# Stepper_Driver_Sheet4.net
KiCad netlist of a schematic drawn in Altium Designer
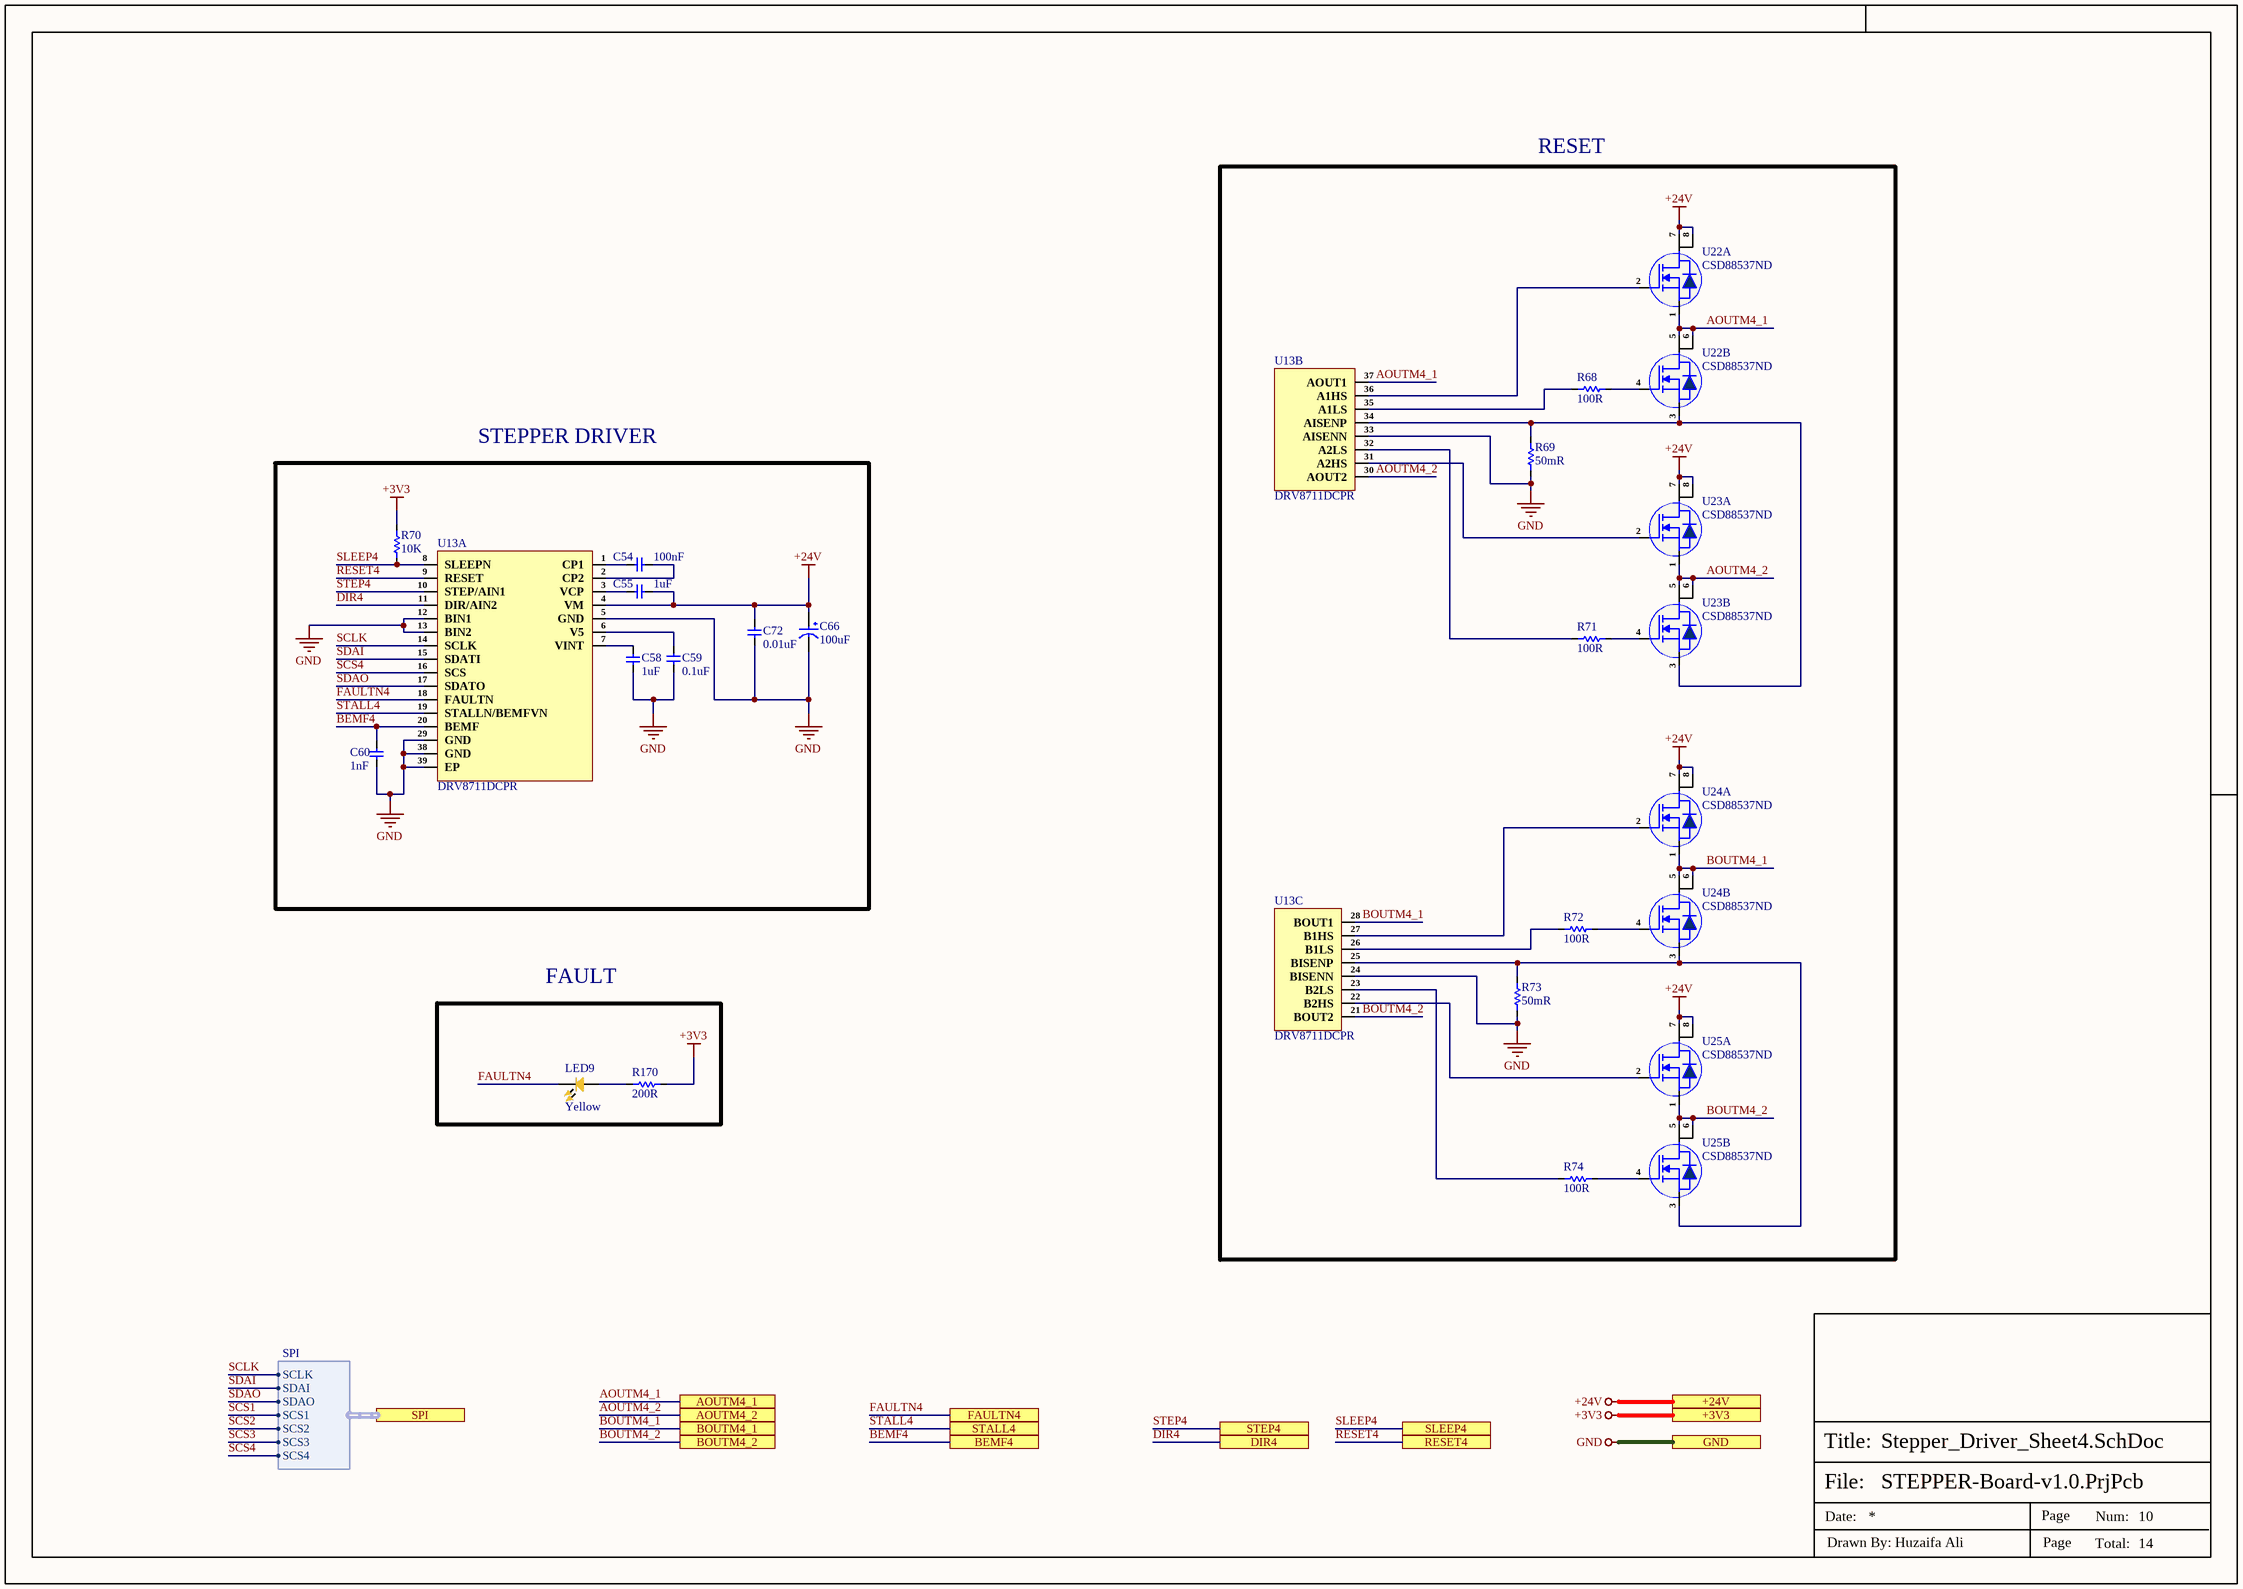
[diagram p0: Stepper_Driver_Sheet4.SchDoc]

(export (version "E")
  (design (tool "Eeschema 10.0.6"))
  (components
    (comp (ref "C54")
      (value "100nF")
      (footprint "cap-0402")
      (description "CAP CER 0.1UF 50V X7R 0402")
      (fields
        (field (name "MANUFACTURER") "TDK")
        (field (name "MANUFACTURER PART NUMBER") "C1005X7R1H104KT000F")
      )
      (libsource (lib "eSpark Libraries") (part "C1005X7R1H104KT000F"))
    )
    (comp (ref "C55")
      (value "1uF")
      (footprint "Cap-0402")
      (description "CAP CER 1UF 10V X5R 0402")
      (fields
        (field (name "MANUFACTURER") "Yageo")
        (field (name "MANUFACTURER PART NUMBER") "CC0402KRX5R6BB105")
      )
      (libsource (lib "eSpark Libraries") (part "CC0402KRX5R6BB105"))
    )
    (comp (ref "C58")
      (value "1uF")
      (footprint "Cap-0402")
      (description "CAP CER 1UF 10V X5R 0402")
      (fields
        (field (name "MANUFACTURER") "Yageo")
        (field (name "MANUFACTURER PART NUMBER") "CC0402KRX5R6BB105")
      )
      (libsource (lib "eSpark Libraries") (part "CC0402KRX5R6BB105"))
    )
    (comp (ref "C59")
      (value "0.1uF")
      (footprint "Cap-0402")
      (description "CAP CER 0.1UF 16V X7R 0402")
      (fields
        (field (name "MANUFACTURER") "Yageo")
        (field (name "MANUFACTURER PART NUMBER") "CC0402JRX7R7BB104")
      )
      (libsource (lib "eSpark Libraries") (part "CC0402JRX7R7BB104"))
    )
    (comp (ref "C60")
      (value "1nF")
      (footprint "Cap-0402")
      (description "CAP CER 1000PF 25V C0G 0402")
      (fields
        (field (name "MANUFACTURER") "TDK")
        (field (name "MANUFACTURER PART NUMBER") "C1005C0G1E102JT000F")
      )
      (libsource (lib "eSpark Libraries") (part "C1005C0G1E102JT000F"))
    )
    (comp (ref "C66")
      (value "100uF")
      (footprint "UWT1H101MNL1GS_")
      (description "CAP ALUM 100UF 20% 50V SMD")
      (fields
        (field (name "MANUFACTURER") "Nichicon")
        (field (name "MANUFACTURER PART NUMBER") "UWT1H101MNL1GS")
      )
      (libsource (lib "eSpark Libraries") (part "UWT1H101MNL1GS"))
    )
    (comp (ref "C72")
      (value "0.01uF")
      (footprint "Cap-0603")
      (description "CAP CER 10000PF 50V C0G/NP0 0603")
      (fields
        (field (name "MANUFACTURER") "Murata")
        (field (name "MANUFACTURER PART NUMBER") "GRM1885C1H103JA01D")
      )
      (libsource (lib "eSpark Libraries") (part "GRM1885C1H103JA01D"))
    )
    (comp (ref "LED9")
      (value "Yellow")
      (footprint "LED-0603")
      (description "yellow 0603 Light Emitting Diodes (LED) ROHS")
      (fields
        (field (name "MANUFACTURER") "Foshan NationStar Optoelectronics")
        (field (name "MANUFACTURER PART NUMBER") "NCD0603Y2")
      )
      (libsource (lib "eSpark Libraries") (part "NCD0603Y2"))
    )
    (comp (ref "R68")
      (value "100R")
      (footprint "Res-0402")
      (description "RES 100 OHM 1% 1/16W 0402")
      (fields
        (field (name "MANUFACTURER") "Yageo")
        (field (name "MANUFACTURER PART NUMBER") "RC0402FR-07100RL")
      )
      (libsource (lib "eSpark Libraries") (part "RC0402FR-07100RL"))
    )
    (comp (ref "R69")
      (value "50mR")
      (footprint "RES-2010")
      (fields
        (field (name "MANUFACTURER") "TA-I Tech")
        (field (name "MANUFACTURER PART NUMBER") "RLM20FECR050")
        (field (name "LCSC PART NUMBER") "C912938")
      )
      (libsource (lib "eSpark Libraries") (part "RLM20FECR050"))
    )
    (comp (ref "R70")
      (value "10K")
      (footprint "Res-0402")
      (description "RES 10K OHM 1% 1/16W 0402")
      (fields
        (field (name "MANUFACTURER") "Yageo")
        (field (name "MANUFACTURER PART NUMBER") "RC0402FR-0710KL")
      )
      (libsource (lib "eSpark Libraries") (part "RC0402FR-0710KL"))
    )
    (comp (ref "R71")
      (value "100R")
      (footprint "Res-0402")
      (description "RES 100 OHM 1% 1/16W 0402")
      (fields
        (field (name "MANUFACTURER") "Yageo")
        (field (name "MANUFACTURER PART NUMBER") "RC0402FR-07100RL")
      )
      (libsource (lib "eSpark Libraries") (part "RC0402FR-07100RL"))
    )
    (comp (ref "R72")
      (value "100R")
      (footprint "Res-0402")
      (description "RES 100 OHM 1% 1/16W 0402")
      (fields
        (field (name "MANUFACTURER") "Yageo")
        (field (name "MANUFACTURER PART NUMBER") "RC0402FR-07100RL")
      )
      (libsource (lib "eSpark Libraries") (part "RC0402FR-07100RL"))
    )
    (comp (ref "R73")
      (value "50mR")
      (footprint "RES-2010")
      (fields
        (field (name "MANUFACTURER") "TA-I Tech")
        (field (name "MANUFACTURER PART NUMBER") "RLM20FECR050")
        (field (name "LCSC PART NUMBER") "C912938")
      )
      (libsource (lib "eSpark Libraries") (part "RLM20FECR050"))
    )
    (comp (ref "R74")
      (value "100R")
      (footprint "Res-0402")
      (description "RES 100 OHM 1% 1/16W 0402")
      (fields
        (field (name "MANUFACTURER") "Yageo")
        (field (name "MANUFACTURER PART NUMBER") "RC0402FR-07100RL")
      )
      (libsource (lib "eSpark Libraries") (part "RC0402FR-07100RL"))
    )
    (comp (ref "R170")
      (value "200R")
      (footprint "Res-0402")
      (description "RES 200 OHM 1% 1/16W 0402")
      (fields
        (field (name "MANUFACTURER") "Yageo")
        (field (name "MANUFACTURER PART NUMBER") "RC0402FR-07200RL")
      )
      (libsource (lib "eSpark Libraries") (part "RC0402FR-07200RL"))
    )
    (comp (ref "U13")
      (value "DRV8711DCPR")
      (footprint "HTSSOP-38-EP-4.4mm")
      (description "IC MTR DRV BIPOLR 8-52V 38HTSSOP")
      (fields (field (name "LCSC PART NUMBER") "C60013") (field (name "MANUFACTURER") "Texas Instruments"))
      (libsource (lib "") (part "DRV8711DCPR_1"))
    )
    (comp (ref "U22")
      (value "CSD88537ND")
      (footprint "SOIC-8")
      (description "MOSFET 2N-CH 60V 15A 8SOIC")
      (fields (field (name "LCSC PART NUMBER") "C117439") (field (name "MANUFACTURER") "Texas Instruments"))
      (libsource (lib "eSpark Libraries") (part "CSD88537ND"))
    )
    (comp (ref "U23")
      (value "CSD88537ND")
      (footprint "SOIC-8")
      (description "MOSFET 2N-CH 60V 15A 8SOIC")
      (fields (field (name "LCSC PART NUMBER") "C117439") (field (name "MANUFACTURER") "Texas Instruments"))
      (libsource (lib "eSpark Libraries") (part "CSD88537ND"))
    )
    (comp (ref "U24")
      (value "CSD88537ND")
      (footprint "SOIC-8")
      (description "MOSFET 2N-CH 60V 15A 8SOIC")
      (fields (field (name "LCSC PART NUMBER") "C117439") (field (name "MANUFACTURER") "Texas Instruments"))
      (libsource (lib "eSpark Libraries") (part "CSD88537ND"))
    )
    (comp (ref "U25")
      (value "CSD88537ND")
      (footprint "SOIC-8")
      (description "MOSFET 2N-CH 60V 15A 8SOIC")
      (fields (field (name "LCSC PART NUMBER") "C117439") (field (name "MANUFACTURER") "Texas Instruments"))
      (libsource (lib "eSpark Libraries") (part "CSD88537ND"))
    )
  )
  (nets
    (net (code "2") (name "+3V3") (class "Default")
      (node (ref "R170") (pin "2") (pinfunction "2_2") (pintype "passive"))
      (node (ref "R70") (pin "1") (pinfunction "1_1") (pintype "passive"))
    )
    (net (code "3") (name "+24V") (class "Default")
      (node (ref "C55") (pin "2") (pinfunction "2_2") (pintype "passive"))
      (node (ref "C66") (pin "1") (pinfunction "1_1") (pintype "passive"))
      (node (ref "C72") (pin "2") (pinfunction "2_2") (pintype "passive"))
      (node (ref "U13") (pin "4") (pinfunction "VM_4") (pintype "passive"))
      (node (ref "U22") (pin "7") (pinfunction "D1_7") (pintype "passive"))
      (node (ref "U22") (pin "8") (pinfunction "D1_8") (pintype "passive"))
      (node (ref "U23") (pin "7") (pinfunction "D1_7") (pintype "passive"))
      (node (ref "U23") (pin "8") (pinfunction "D1_8") (pintype "passive"))
      (node (ref "U24") (pin "7") (pinfunction "D1_7") (pintype "passive"))
      (node (ref "U24") (pin "8") (pinfunction "D1_8") (pintype "passive"))
      (node (ref "U25") (pin "7") (pinfunction "D1_7") (pintype "passive"))
      (node (ref "U25") (pin "8") (pinfunction "D1_8") (pintype "passive"))
    )
    (net (code "4") (name "/AOUTM4_1") (class "Default")
      (node (ref "U13") (pin "37") (pinfunction "AOUT1_37") (pintype "passive"))
      (node (ref "U22") (pin "1") (pinfunction "S1_1") (pintype "passive"))
      (node (ref "U22") (pin "5") (pinfunction "D2_5") (pintype "passive"))
      (node (ref "U22") (pin "6") (pinfunction "D2_6") (pintype "passive"))
    )
    (net (code "5") (name "/AOUTM4_2") (class "Default")
      (node (ref "U13") (pin "30") (pinfunction "AOUT2_30") (pintype "passive"))
      (node (ref "U23") (pin "1") (pinfunction "S1_1") (pintype "passive"))
      (node (ref "U23") (pin "5") (pinfunction "D2_5") (pintype "passive"))
      (node (ref "U23") (pin "6") (pinfunction "D2_6") (pintype "passive"))
    )
    (net (code "6") (name "/BEMF4") (class "Default")
      (node (ref "C60") (pin "2") (pinfunction "2_2") (pintype "passive"))
      (node (ref "U13") (pin "20") (pinfunction "BEMF_20") (pintype "passive"))
    )
    (net (code "7") (name "/BOUTM4_1") (class "Default")
      (node (ref "U13") (pin "28") (pinfunction "BOUT1_28") (pintype "passive"))
      (node (ref "U24") (pin "1") (pinfunction "S1_1") (pintype "passive"))
      (node (ref "U24") (pin "5") (pinfunction "D2_5") (pintype "passive"))
      (node (ref "U24") (pin "6") (pinfunction "D2_6") (pintype "passive"))
    )
    (net (code "8") (name "/BOUTM4_2") (class "Default")
      (node (ref "U13") (pin "21") (pinfunction "BOUT2_21") (pintype "passive"))
      (node (ref "U25") (pin "1") (pinfunction "S1_1") (pintype "passive"))
      (node (ref "U25") (pin "5") (pinfunction "D2_5") (pintype "passive"))
      (node (ref "U25") (pin "6") (pinfunction "D2_6") (pintype "passive"))
    )
    (net (code "9") (name "/DIR4") (class "Default")
      (node (ref "U13") (pin "11") (pinfunction "DIR/AIN2_11") (pintype "passive"))
    )
    (net (code "10") (name "/FAULTN4") (class "Default")
      (node (ref "LED9") (pin "2") (pinfunction "2_2") (pintype "passive"))
      (node (ref "U13") (pin "18") (pinfunction "FAULTN_18") (pintype "passive"))
    )
    (net (code "11") (name "/RESET4") (class "Default")
      (node (ref "U13") (pin "9") (pinfunction "RESET_9") (pintype "passive"))
    )
    (net (code "12") (name "/SCLK") (class "Default")
      (node (ref "U13") (pin "14") (pinfunction "SCLK_14") (pintype "passive"))
    )
    (net (code "16") (name "/SCS4") (class "Default")
      (node (ref "U13") (pin "16") (pinfunction "SCS_16") (pintype "passive"))
    )
    (net (code "17") (name "/SDAI") (class "Default")
      (node (ref "U13") (pin "15") (pinfunction "SDATI_15") (pintype "passive"))
    )
    (net (code "18") (name "/SDAO") (class "Default")
      (node (ref "U13") (pin "17") (pinfunction "SDATO_17") (pintype "passive"))
    )
    (net (code "19") (name "/SLEEP4") (class "Default")
      (node (ref "R70") (pin "2") (pinfunction "2_2") (pintype "passive"))
      (node (ref "U13") (pin "8") (pinfunction "SLEEPN_8") (pintype "passive"))
    )
    (net (code "20") (name "/STALL4") (class "Default")
      (node (ref "U13") (pin "19") (pinfunction "STALLN/BEMFVN_19") (pintype "passive"))
    )
    (net (code "21") (name "/STEP4") (class "Default")
      (node (ref "U13") (pin "10") (pinfunction "STEP/AIN1_10") (pintype "passive"))
    )
    (net (code "23") (name "GND") (class "Default")
      (node (ref "C58") (pin "1") (pinfunction "1_1") (pintype "passive"))
      (node (ref "C59") (pin "2") (pinfunction "2_2") (pintype "passive"))
      (node (ref "C60") (pin "1") (pinfunction "1_1") (pintype "passive"))
      (node (ref "C66") (pin "2") (pinfunction "2_2") (pintype "passive"))
      (node (ref "C72") (pin "1") (pinfunction "1_1") (pintype "passive"))
      (node (ref "R69") (pin "1") (pinfunction "1_1") (pintype "passive"))
      (node (ref "R73") (pin "1") (pinfunction "1_1") (pintype "passive"))
      (node (ref "U13") (pin "12") (pinfunction "BIN1_12") (pintype "passive"))
      (node (ref "U13") (pin "13") (pinfunction "BIN2_13") (pintype "passive"))
      (node (ref "U13") (pin "24") (pinfunction "BISENN_24") (pintype "passive"))
      (node (ref "U13") (pin "29") (pinfunction "GND_29") (pintype "passive"))
      (node (ref "U13") (pin "33") (pinfunction "AISENN_33") (pintype "passive"))
      (node (ref "U13") (pin "38") (pinfunction "GND_38") (pintype "passive"))
      (node (ref "U13") (pin "39") (pinfunction "EP_39") (pintype "passive"))
      (node (ref "U13") (pin "5") (pinfunction "GND_5") (pintype "passive"))
    )
    (net (code "24") (name "Net-(LED9-Pad1)") (class "Default")
      (node (ref "LED9") (pin "1") (pinfunction "1_1") (pintype "passive"))
      (node (ref "R170") (pin "1") (pinfunction "1_1") (pintype "passive"))
    )
    (net (code "25") (name "Net-(U13A-CP1)") (class "Default")
      (node (ref "C54") (pin "1") (pinfunction "1_1") (pintype "passive"))
      (node (ref "U13") (pin "1") (pinfunction "CP1_1") (pintype "passive"))
    )
    (net (code "26") (name "Net-(U13A-CP2)") (class "Default")
      (node (ref "C54") (pin "2") (pinfunction "2_2") (pintype "passive"))
      (node (ref "U13") (pin "2") (pinfunction "CP2_2") (pintype "passive"))
    )
    (net (code "27") (name "Net-(U13A-V5)") (class "Default")
      (node (ref "C59") (pin "1") (pinfunction "1_1") (pintype "passive"))
      (node (ref "U13") (pin "6") (pinfunction "V5_6") (pintype "passive"))
    )
    (net (code "28") (name "Net-(U13A-VCP)") (class "Default")
      (node (ref "C55") (pin "1") (pinfunction "1_1") (pintype "passive"))
      (node (ref "U13") (pin "3") (pinfunction "VCP_3") (pintype "passive"))
    )
    (net (code "29") (name "Net-(U13A-VINT)") (class "Default")
      (node (ref "C58") (pin "2") (pinfunction "2_2") (pintype "passive"))
      (node (ref "U13") (pin "7") (pinfunction "VINT_7") (pintype "passive"))
    )
    (net (code "30") (name "Net-(U13B-A1HS)") (class "Default")
      (node (ref "U13") (pin "36") (pinfunction "A1HS_36") (pintype "passive"))
      (node (ref "U22") (pin "2") (pinfunction "G1_2") (pintype "passive"))
    )
    (net (code "31") (name "Net-(U13B-A1LS)") (class "Default")
      (node (ref "R68") (pin "1") (pinfunction "1_1") (pintype "passive"))
      (node (ref "U13") (pin "35") (pinfunction "A1LS_35") (pintype "passive"))
    )
    (net (code "32") (name "Net-(U13B-A2HS)") (class "Default")
      (node (ref "U13") (pin "31") (pinfunction "A2HS_31") (pintype "passive"))
      (node (ref "U23") (pin "2") (pinfunction "G1_2") (pintype "passive"))
    )
    (net (code "33") (name "Net-(U13B-A2LS)") (class "Default")
      (node (ref "R71") (pin "1") (pinfunction "1_1") (pintype "passive"))
      (node (ref "U13") (pin "32") (pinfunction "A2LS_32") (pintype "passive"))
    )
    (net (code "34") (name "Net-(U13B-AISENP)") (class "Default")
      (node (ref "R69") (pin "2") (pinfunction "2_2") (pintype "passive"))
      (node (ref "U13") (pin "34") (pinfunction "AISENP_34") (pintype "passive"))
      (node (ref "U22") (pin "3") (pinfunction "S2_3") (pintype "passive"))
      (node (ref "U23") (pin "3") (pinfunction "S2_3") (pintype "passive"))
    )
    (net (code "35") (name "Net-(U13C-B1HS)") (class "Default")
      (node (ref "U13") (pin "27") (pinfunction "B1HS_27") (pintype "passive"))
      (node (ref "U24") (pin "2") (pinfunction "G1_2") (pintype "passive"))
    )
    (net (code "36") (name "Net-(U13C-B1LS)") (class "Default")
      (node (ref "R72") (pin "1") (pinfunction "1_1") (pintype "passive"))
      (node (ref "U13") (pin "26") (pinfunction "B1LS_26") (pintype "passive"))
    )
    (net (code "37") (name "Net-(U13C-B2HS)") (class "Default")
      (node (ref "U13") (pin "22") (pinfunction "B2HS_22") (pintype "passive"))
      (node (ref "U25") (pin "2") (pinfunction "G1_2") (pintype "passive"))
    )
    (net (code "38") (name "Net-(U13C-B2LS)") (class "Default")
      (node (ref "R74") (pin "1") (pinfunction "1_1") (pintype "passive"))
      (node (ref "U13") (pin "23") (pinfunction "B2LS_23") (pintype "passive"))
    )
    (net (code "39") (name "Net-(U13C-BISENP)") (class "Default")
      (node (ref "R73") (pin "2") (pinfunction "2_2") (pintype "passive"))
      (node (ref "U13") (pin "25") (pinfunction "BISENP_25") (pintype "passive"))
      (node (ref "U24") (pin "3") (pinfunction "S2_3") (pintype "passive"))
      (node (ref "U25") (pin "3") (pinfunction "S2_3") (pintype "passive"))
    )
    (net (code "40") (name "Net-(U22B-G4)") (class "Default")
      (node (ref "R68") (pin "2") (pinfunction "2_2") (pintype "passive"))
      (node (ref "U22") (pin "4") (pinfunction "G4_4") (pintype "passive"))
    )
    (net (code "41") (name "Net-(U23B-G4)") (class "Default")
      (node (ref "R71") (pin "2") (pinfunction "2_2") (pintype "passive"))
      (node (ref "U23") (pin "4") (pinfunction "G4_4") (pintype "passive"))
    )
    (net (code "42") (name "Net-(U24B-G4)") (class "Default")
      (node (ref "R72") (pin "2") (pinfunction "2_2") (pintype "passive"))
      (node (ref "U24") (pin "4") (pinfunction "G4_4") (pintype "passive"))
    )
    (net (code "43") (name "Net-(U25B-G4)") (class "Default")
      (node (ref "R74") (pin "2") (pinfunction "2_2") (pintype "passive"))
      (node (ref "U25") (pin "4") (pinfunction "G4_4") (pintype "passive"))
    )
  )
)
